# 10-Push_Buttons.net
KiCad netlist of a schematic drawn in Altium Designer
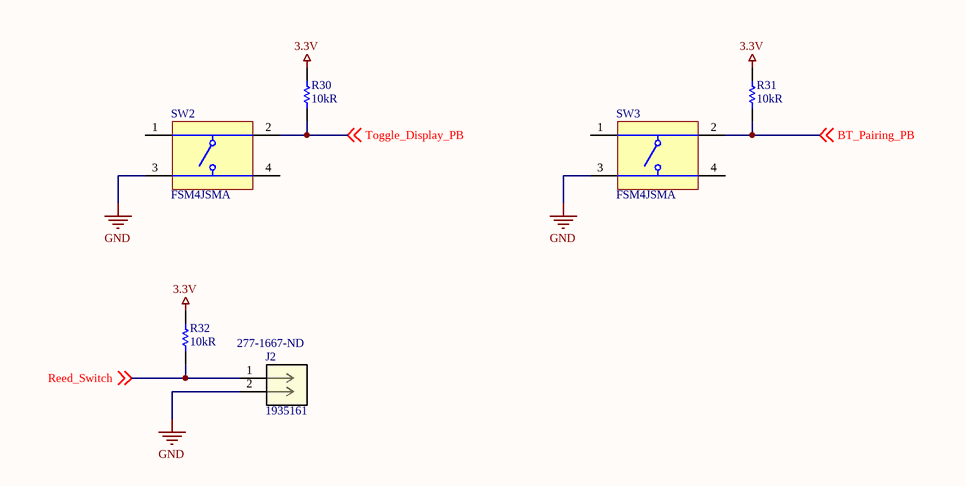
[diagram p0: 10-Push_Buttons.SchDoc]

(export (version "E")
  (design (tool "Eeschema 10.0.6"))
  (components
    (comp (ref "J2")
      (value "1935161")
      (footprint "CONN_1935161_PXC")
      (description "TERM BLK 2POS SIDE ENTRY 5MM PCB")
      (fields
        (field (name "SUPPLIER PART NUMBER 1") "277-1667-ND")
        (field (name "COPYRIGHT") "Copyright (C) 2022 Ultra Librarian. All rights reserved.")
      )
      (libsource (lib "team6") (part "1935161"))
    )
    (comp (ref "R30")
      (value "RC0805FR-0710KL")
      (footprint "RESC2013X60X35NL10T20")
      (description "Chip Resistor, 10 KOhm, +/- 1%, 0.125 W, -55 to 155 degC, 0805 (2012 Metric), RoHS, Tape and Reel")
      (fields
        (field (name "MANUFACTURER") "Yageo")
        (field (name "RESISTANCE") "10kR")
        (field (name "TOLERANCE") "1%")
      )
      (libsource (lib "Altium Content Vault") (part "RES-2"))
    )
    (comp (ref "R31")
      (value "RC0805FR-0710KL")
      (footprint "RESC2013X60X35NL10T20")
      (description "Chip Resistor, 10 KOhm, +/- 1%, 0.125 W, -55 to 155 degC, 0805 (2012 Metric), RoHS, Tape and Reel")
      (fields
        (field (name "MANUFACTURER") "Yageo")
        (field (name "RESISTANCE") "10kR")
        (field (name "TOLERANCE") "1%")
      )
      (libsource (lib "Altium Content Vault") (part "RES-2"))
    )
    (comp (ref "R32")
      (value "RC0805FR-0710KL")
      (footprint "RESC2013X60X35NL10T20")
      (description "Chip Resistor, 10 KOhm, +/- 1%, 0.125 W, -55 to 155 degC, 0805 (2012 Metric), RoHS, Tape and Reel")
      (fields
        (field (name "MANUFACTURER") "Yageo")
        (field (name "RESISTANCE") "10kR")
        (field (name "TOLERANCE") "1%")
      )
      (libsource (lib "Altium Content Vault") (part "RES-2"))
    )
    (comp (ref "SW2")
      (value "FSM4JSMA")
      (footprint "TECO-FSM4JSMA_V")
      (description "Swicth, SPST, 24 V, -35 to 85 degC, 4-Pin SMD, RoHS, Tape and Reel")
      (fields (field (name "MANUFACTURER") "TE Connectivity"))
      (libsource (lib "Altium Content Vault") (part "SW-SPST-4_A"))
    )
    (comp (ref "SW3")
      (value "FSM4JSMA")
      (footprint "TECO-FSM4JSMA_V")
      (description "Swicth, SPST, 24 V, -35 to 85 degC, 4-Pin SMD, RoHS, Tape and Reel")
      (fields (field (name "MANUFACTURER") "TE Connectivity"))
      (libsource (lib "Altium Content Vault") (part "SW-SPST-4_A"))
    )
  )
  (nets
    (net (code "1") (name "3.3V") (class "Default")
      (node (ref "R30") (pin "2") (pinfunction "2_2") (pintype "passive"))
      (node (ref "R31") (pin "2") (pinfunction "2_2") (pintype "passive"))
      (node (ref "R32") (pin "2") (pinfunction "2_2") (pintype "passive"))
    )
    (net (code "2") (name "BT_Pairing_PB") (class "Default")
      (node (ref "R31") (pin "1") (pinfunction "1_1") (pintype "passive"))
      (node (ref "SW3") (pin "2") (pinfunction "2_2") (pintype "passive"))
    )
    (net (code "3") (name "GND") (class "Default")
      (node (ref "J2") (pin "2") (pinfunction "2_2") (pintype "passive"))
      (node (ref "SW2") (pin "3") (pinfunction "3_3") (pintype "passive"))
      (node (ref "SW3") (pin "3") (pinfunction "3_3") (pintype "passive"))
    )
    (net (code "4") (name "Reed_Switch") (class "Default")
      (node (ref "J2") (pin "1") (pinfunction "1_1") (pintype "passive"))
      (node (ref "R32") (pin "1") (pinfunction "1_1") (pintype "passive"))
    )
    (net (code "5") (name "Toggle_Display_PB") (class "Default")
      (node (ref "R30") (pin "1") (pinfunction "1_1") (pintype "passive"))
      (node (ref "SW2") (pin "2") (pinfunction "2_2") (pintype "passive"))
    )
    (net (code "6") (name "unconnected-(SW2-Pad1)") (class "Default")
      (node (ref "SW2") (pin "1") (pinfunction "1_1") (pintype "passive"))
    )
    (net (code "7") (name "unconnected-(SW2-Pad4)") (class "Default")
      (node (ref "SW2") (pin "4") (pinfunction "4_4") (pintype "passive"))
    )
    (net (code "8") (name "unconnected-(SW3-Pad1)") (class "Default")
      (node (ref "SW3") (pin "1") (pinfunction "1_1") (pintype "passive"))
    )
    (net (code "9") (name "unconnected-(SW3-Pad4)") (class "Default")
      (node (ref "SW3") (pin "4") (pinfunction "4_4") (pintype "passive"))
    )
  )
)
